# rpi-clock-33v.net
KiCad netlist of a schematic drawn in EAGLE
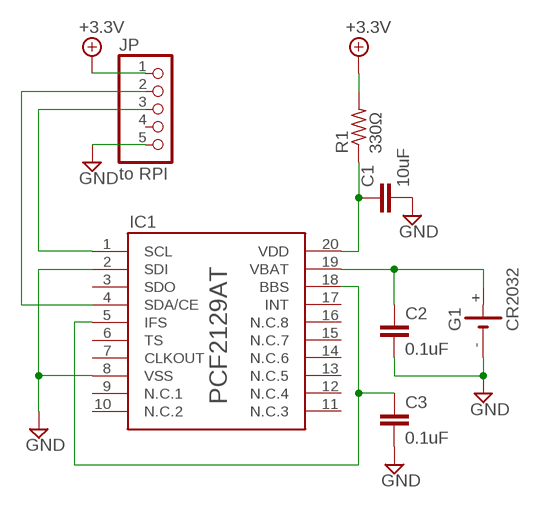
[diagram p0: schematic, sheet 1]

(export (version "E")
  (design (tool "Eeschema 10.0.6"))
  (components
    (comp (ref "C1")
      (value "10uF")
      (footprint "eagle-import:C0504")
      (libsource (lib "eagle-import") (part "C-EUC0504"))
    )
    (comp (ref "C2")
      (value "0.1uF")
      (footprint "eagle-import:C0504")
      (libsource (lib "eagle-import") (part "C-EUC0504"))
    )
    (comp (ref "C3")
      (value "0.1uF")
      (footprint "eagle-import:C0504")
      (libsource (lib "eagle-import") (part "C-EUC0504"))
    )
    (comp (ref "G1")
      (value "CR2032")
      (footprint "eagle-import:HU2032")
      (libsource (lib "eagle-import") (part "HU2032"))
    )
    (comp (ref "IC1")
      (value "PCF2129AT")
      (footprint "eagle-import:SO20")
      (libsource (lib "eagle-import") (part "PCF2129AT"))
    )
    (comp (ref "JP")
      (value "to RPI")
      (footprint "eagle-import:1X05")
      (libsource (lib "eagle-import") (part "PINHD-1X5"))
    )
    (comp (ref "R1")
      (value "330Ω")
      (footprint "eagle-import:M0805")
      (libsource (lib "eagle-import") (part "R-US_M0805"))
    )
  )
  (nets
    (net (code "1") (name "+3.3V") (class "Default")
      (node (ref "JP") (pin "1") (pinfunction "1_1") (pintype "passive"))
      (node (ref "R1") (pin "2") (pinfunction "2_2") (pintype "passive"))
    )
    (net (code "2") (name "GND") (class "Default")
      (node (ref "C1") (pin "2") (pinfunction "2_2") (pintype "passive"))
      (node (ref "C2") (pin "2") (pinfunction "2_2") (pintype "passive"))
      (node (ref "C3") (pin "2") (pinfunction "2_2") (pintype "passive"))
      (node (ref "G1") (pin "-") (pinfunction "-_-") (pintype "passive"))
      (node (ref "IC1") (pin "2") (pinfunction "SDI_2") (pintype "bidirectional"))
      (node (ref "IC1") (pin "8") (pinfunction "VSS_8") (pintype "bidirectional"))
      (node (ref "JP") (pin "5") (pinfunction "5_5") (pintype "passive"))
    )
    (net (code "3") (name "Net-(IC1-BBS)") (class "Default")
      (node (ref "C3") (pin "1") (pinfunction "1_1") (pintype "passive"))
      (node (ref "IC1") (pin "18") (pinfunction "BBS_18") (pintype "bidirectional"))
      (node (ref "IC1") (pin "5") (pinfunction "IFS_5") (pintype "bidirectional"))
    )
    (net (code "4") (name "Net-(IC1-SCL)") (class "Default")
      (node (ref "IC1") (pin "1") (pinfunction "SCL_1") (pintype "bidirectional"))
      (node (ref "JP") (pin "3") (pinfunction "3_3") (pintype "passive"))
    )
    (net (code "5") (name "Net-(IC1-SDA{slash}CE)") (class "Default")
      (node (ref "IC1") (pin "4") (pinfunction "SDA/CE_4") (pintype "bidirectional"))
      (node (ref "JP") (pin "2") (pinfunction "2_2") (pintype "passive"))
    )
    (net (code "6") (name "Net-(IC1-VBAT)") (class "Default")
      (node (ref "C2") (pin "1") (pinfunction "1_1") (pintype "passive"))
      (node (ref "G1") (pin "+") (pinfunction "+_+") (pintype "passive"))
      (node (ref "IC1") (pin "19") (pinfunction "VBAT_19") (pintype "bidirectional"))
    )
    (net (code "7") (name "Net-(IC1-VDD)") (class "Default")
      (node (ref "C1") (pin "1") (pinfunction "1_1") (pintype "passive"))
      (node (ref "IC1") (pin "20") (pinfunction "VDD_20") (pintype "bidirectional"))
      (node (ref "R1") (pin "1") (pinfunction "1_1") (pintype "passive"))
    )
    (net (code "8") (name "unconnected-(G1-+-Pad+@2)") (class "Default")
      (node (ref "G1") (pin "+@2") (pinfunction "+_+@2") (pintype "passive"))
    )
    (net (code "9") (name "unconnected-(IC1-CLKOUT-Pad7)") (class "Default")
      (node (ref "IC1") (pin "7") (pinfunction "CLKOUT_7") (pintype "bidirectional"))
    )
    (net (code "10") (name "unconnected-(IC1-INT-Pad17)") (class "Default")
      (node (ref "IC1") (pin "17") (pinfunction "INT_17") (pintype "bidirectional"))
    )
    (net (code "11") (name "unconnected-(IC1-N.C.1-Pad9)") (class "Default")
      (node (ref "IC1") (pin "9") (pinfunction "N.C.1_9") (pintype "bidirectional"))
    )
    (net (code "12") (name "unconnected-(IC1-N.C.2-Pad10)") (class "Default")
      (node (ref "IC1") (pin "10") (pinfunction "N.C.2_10") (pintype "bidirectional"))
    )
    (net (code "13") (name "unconnected-(IC1-N.C.3-Pad11)") (class "Default")
      (node (ref "IC1") (pin "11") (pinfunction "N.C.3_11") (pintype "bidirectional"))
    )
    (net (code "14") (name "unconnected-(IC1-N.C.4-Pad12)") (class "Default")
      (node (ref "IC1") (pin "12") (pinfunction "N.C.4_12") (pintype "bidirectional"))
    )
    (net (code "15") (name "unconnected-(IC1-N.C.5-Pad13)") (class "Default")
      (node (ref "IC1") (pin "13") (pinfunction "N.C.5_13") (pintype "bidirectional"))
    )
    (net (code "16") (name "unconnected-(IC1-N.C.6-Pad14)") (class "Default")
      (node (ref "IC1") (pin "14") (pinfunction "N.C.6_14") (pintype "bidirectional"))
    )
    (net (code "17") (name "unconnected-(IC1-N.C.7-Pad15)") (class "Default")
      (node (ref "IC1") (pin "15") (pinfunction "N.C.7_15") (pintype "bidirectional"))
    )
    (net (code "18") (name "unconnected-(IC1-N.C.8-Pad16)") (class "Default")
      (node (ref "IC1") (pin "16") (pinfunction "N.C.8_16") (pintype "bidirectional"))
    )
    (net (code "19") (name "unconnected-(IC1-SDO-Pad3)") (class "Default")
      (node (ref "IC1") (pin "3") (pinfunction "SDO_3") (pintype "bidirectional"))
    )
    (net (code "20") (name "unconnected-(IC1-TS-Pad6)") (class "Default")
      (node (ref "IC1") (pin "6") (pinfunction "TS_6") (pintype "bidirectional"))
    )
    (net (code "21") (name "unconnected-(JP-Pad4)") (class "Default")
      (node (ref "JP") (pin "4") (pinfunction "4_4") (pintype "passive"))
    )
  )
)
